# Wici_ski.net
KiCad netlist of a schematic drawn in EAGLE
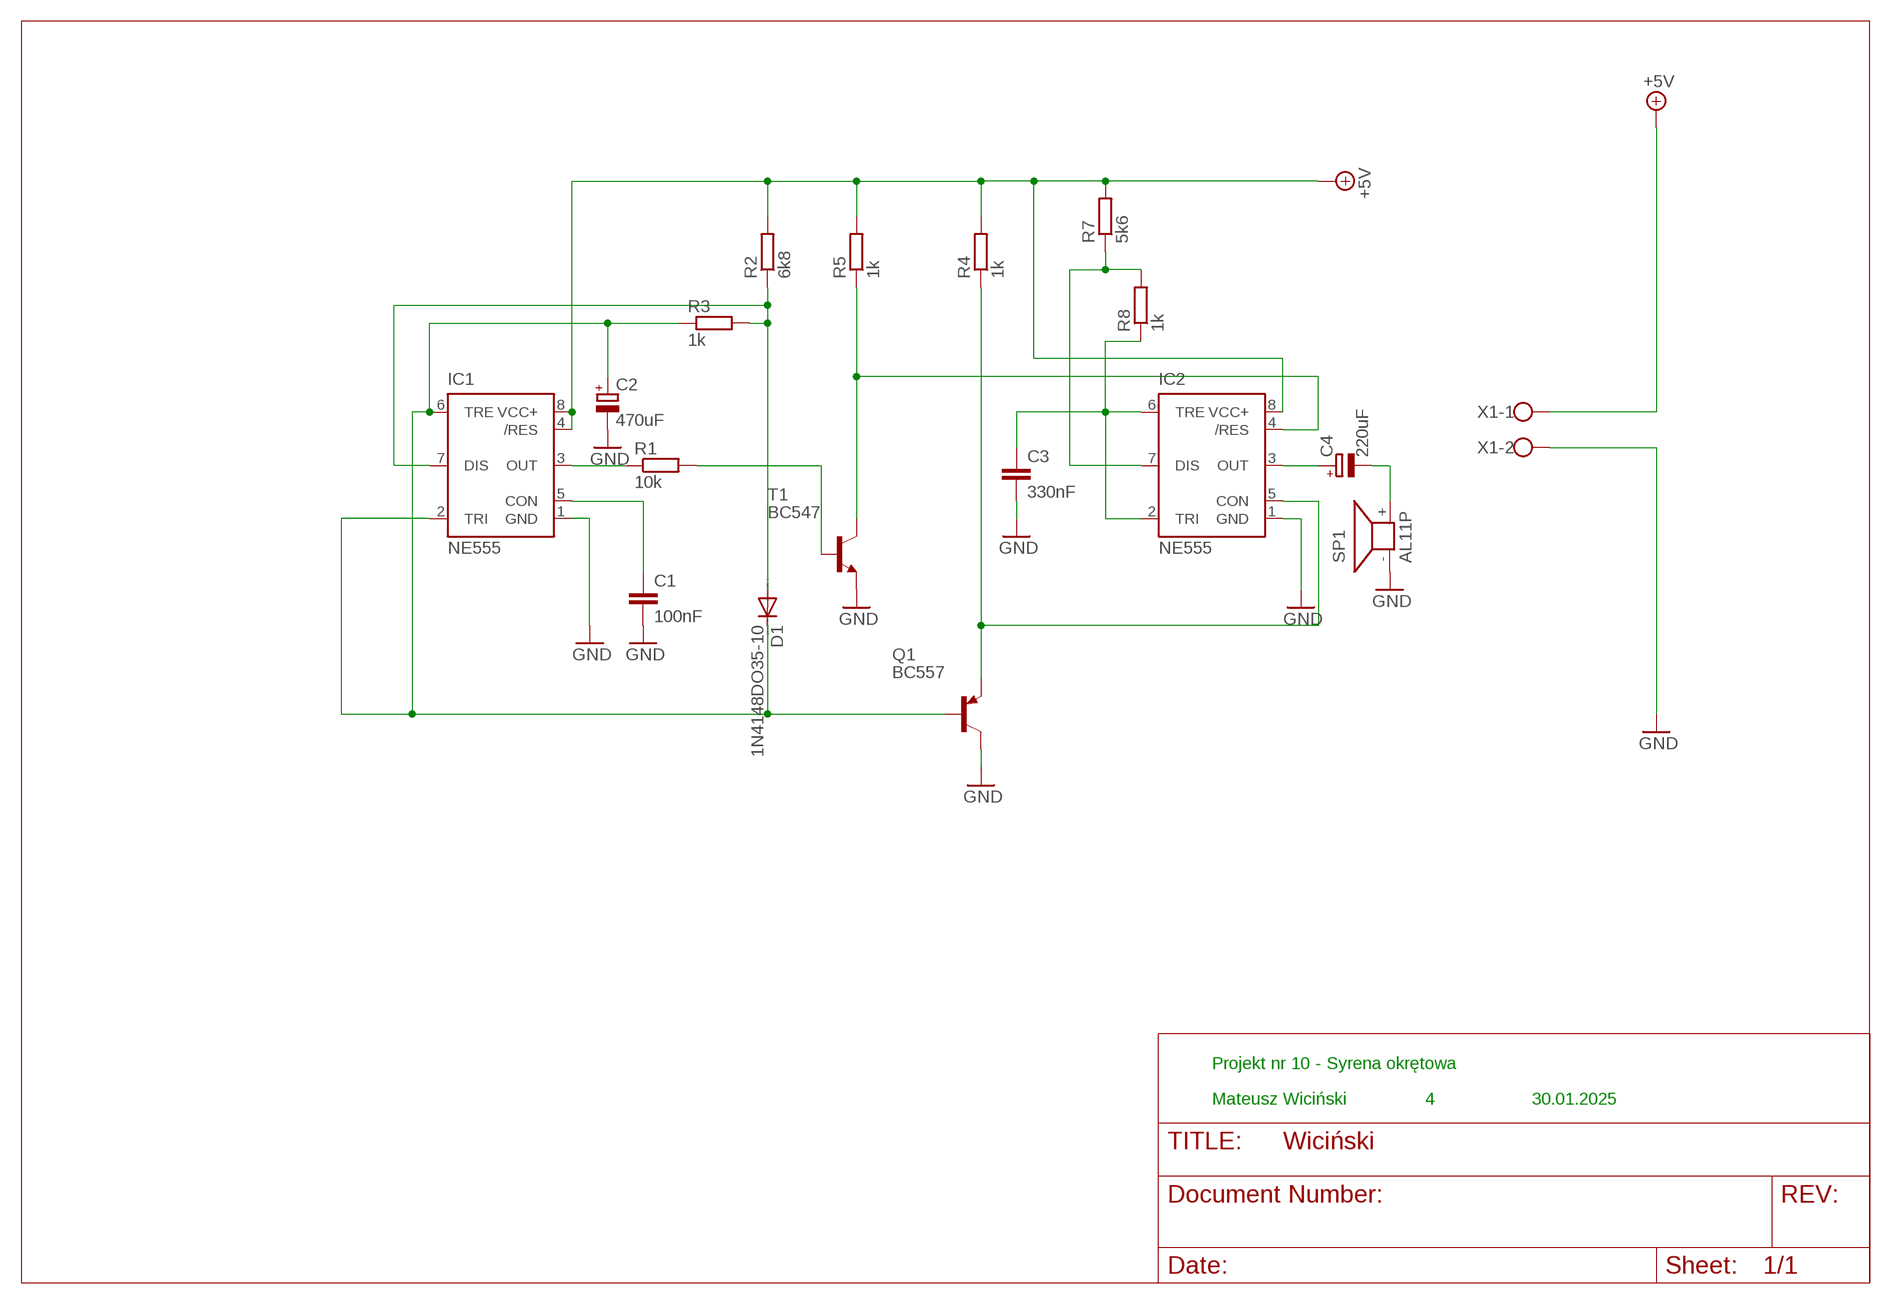
[diagram p0: schematic, sheet 1]

(export (version "E")
  (design (tool "Eeschema 10.0.6"))
  (components
    (comp (ref "C1")
      (value "100nF")
      (footprint "eagle-import:C050-050X075")
      (libsource (lib "eagle-import") (part "C-EU050-050X075"))
    )
    (comp (ref "C2")
      (value "470uF")
      (footprint "eagle-import:140CLH-1014")
      (libsource (lib "eagle-import") (part "CPOL-EU140CLH-1014"))
    )
    (comp (ref "C3")
      (value "330nF")
      (footprint "eagle-import:C050-050X075")
      (libsource (lib "eagle-import") (part "C-EU050-050X075"))
    )
    (comp (ref "C4")
      (value "220uF")
      (footprint "eagle-import:140CLH-1014")
      (libsource (lib "eagle-import") (part "CPOL-EU140CLH-1014"))
    )
    (comp (ref "D1")
      (value "1N4148DO35-10")
      (footprint "eagle-import:DO35-10")
      (libsource (lib "eagle-import") (part "1N4148DO35-10"))
    )
    (comp (ref "IC1")
      (value "NE555")
      (footprint "eagle-import:DIL-08")
      (fields (field (name "MF") "Arrow Electronics") (field (name "MPN") "NE555N"))
      (libsource (lib "eagle-import") (part "NE555"))
    )
    (comp (ref "IC2")
      (value "NE555")
      (footprint "eagle-import:DIL-08")
      (fields (field (name "MF") "Arrow Electronics") (field (name "MPN") "NE555N"))
      (libsource (lib "eagle-import") (part "NE555"))
    )
    (comp (ref "Q1")
      (value "BC557")
      (footprint "eagle-import:TO92")
      (libsource (lib "eagle-import") (part "BC557"))
    )
    (comp (ref "R1")
      (value "10k")
      (footprint "eagle-import:0207_10")
      (libsource (lib "eagle-import") (part "R-EU_0207/10"))
    )
    (comp (ref "R2")
      (value "6k8")
      (footprint "eagle-import:0207_10")
      (libsource (lib "eagle-import") (part "R-EU_0207/10"))
    )
    (comp (ref "R3")
      (value "1k")
      (footprint "eagle-import:0207_10")
      (libsource (lib "eagle-import") (part "R-EU_0207/10"))
    )
    (comp (ref "R4")
      (value "1k")
      (footprint "eagle-import:0207_10")
      (libsource (lib "eagle-import") (part "R-EU_0207/10"))
    )
    (comp (ref "R5")
      (value "1k")
      (footprint "eagle-import:0207_10")
      (libsource (lib "eagle-import") (part "R-EU_0207/10"))
    )
    (comp (ref "R7")
      (value "5k6")
      (footprint "eagle-import:0207_10")
      (libsource (lib "eagle-import") (part "R-EU_0207/10"))
    )
    (comp (ref "R8")
      (value "1k")
      (footprint "eagle-import:0207_10")
      (libsource (lib "eagle-import") (part "R-EU_0207/10"))
    )
    (comp (ref "SP1")
      (value "AL11P")
      (footprint "eagle-import:AL11P")
      (libsource (lib "eagle-import") (part "AL11P"))
    )
    (comp (ref "T1")
      (value "BC547")
      (footprint "eagle-import:TO92")
      (libsource (lib "eagle-import") (part "BC547"))
    )
    (comp (ref "X1")
      (value "W237-102")
      (footprint "eagle-import:W237-102")
      (fields (field (name "MPN") "237-102"))
      (libsource (lib "eagle-import") (part "W237-102"))
    )
  )
  (nets
    (net (code "1") (name "+5V") (class "Default")
      (node (ref "IC1") (pin "4") (pinfunction "/RES_4") (pintype "input"))
      (node (ref "IC1") (pin "8") (pinfunction "VCC+_8") (pintype "power_in"))
      (node (ref "IC2") (pin "8") (pinfunction "VCC+_8") (pintype "power_in"))
      (node (ref "R2") (pin "2") (pinfunction "2_2") (pintype "passive"))
      (node (ref "R4") (pin "2") (pinfunction "2_2") (pintype "passive"))
      (node (ref "R5") (pin "2") (pinfunction "2_2") (pintype "passive"))
      (node (ref "R7") (pin "2") (pinfunction "2_2") (pintype "passive"))
      (node (ref "X1") (pin "1") (pinfunction "KL_1") (pintype "passive"))
    )
    (net (code "2") (name "GND") (class "Default")
      (node (ref "C1") (pin "2") (pinfunction "2_2") (pintype "passive"))
      (node (ref "C2") (pin "-") (pinfunction "-_-") (pintype "passive"))
      (node (ref "C3") (pin "2") (pinfunction "2_2") (pintype "passive"))
      (node (ref "IC1") (pin "1") (pinfunction "GND_1") (pintype "power_in"))
      (node (ref "IC2") (pin "1") (pinfunction "GND_1") (pintype "power_in"))
      (node (ref "Q1") (pin "3") (pinfunction "C_3") (pintype "passive"))
      (node (ref "SP1") (pin "-") (pinfunction "1_-") (pintype "passive"))
      (node (ref "T1") (pin "1") (pinfunction "E_1") (pintype "passive"))
      (node (ref "X1") (pin "2") (pinfunction "KL_2") (pintype "passive"))
    )
    (net (code "3") (name "Net-(IC1-CON)") (class "Default")
      (node (ref "C1") (pin "1") (pinfunction "1_1") (pintype "passive"))
      (node (ref "IC1") (pin "5") (pinfunction "CON_5") (pintype "input"))
    )
    (net (code "4") (name "Net-(IC1-DIS)") (class "Default")
      (node (ref "D1") (pin "A") (pinfunction "A_A") (pintype "passive"))
      (node (ref "IC1") (pin "7") (pinfunction "DIS_7") (pintype "input"))
      (node (ref "R2") (pin "1") (pinfunction "1_1") (pintype "passive"))
      (node (ref "R3") (pin "2") (pinfunction "2_2") (pintype "passive"))
    )
    (net (code "5") (name "Net-(IC1-OUT)") (class "Default")
      (node (ref "IC1") (pin "3") (pinfunction "OUT_3") (pintype "output"))
      (node (ref "R1") (pin "1") (pinfunction "1_1") (pintype "passive"))
    )
    (net (code "6") (name "Net-(IC1-TRE)") (class "Default")
      (node (ref "C2") (pin "+") (pinfunction "+_+") (pintype "passive"))
      (node (ref "D1") (pin "C") (pinfunction "C_C") (pintype "passive"))
      (node (ref "IC1") (pin "2") (pinfunction "TRI_2") (pintype "input"))
      (node (ref "IC1") (pin "6") (pinfunction "TRE_6") (pintype "input"))
      (node (ref "Q1") (pin "2") (pinfunction "B_2") (pintype "passive"))
      (node (ref "R3") (pin "1") (pinfunction "1_1") (pintype "passive"))
    )
    (net (code "7") (name "Net-(IC2-CON)") (class "Default")
      (node (ref "IC2") (pin "5") (pinfunction "CON_5") (pintype "input"))
      (node (ref "Q1") (pin "1") (pinfunction "E_1") (pintype "passive"))
      (node (ref "R4") (pin "1") (pinfunction "1_1") (pintype "passive"))
    )
    (net (code "8") (name "Net-(IC2-DIS)") (class "Default")
      (node (ref "IC2") (pin "7") (pinfunction "DIS_7") (pintype "input"))
      (node (ref "R7") (pin "1") (pinfunction "1_1") (pintype "passive"))
      (node (ref "R8") (pin "2") (pinfunction "2_2") (pintype "passive"))
    )
    (net (code "9") (name "Net-(IC2-OUT)") (class "Default")
      (node (ref "C4") (pin "+") (pinfunction "+_+") (pintype "passive"))
      (node (ref "IC2") (pin "3") (pinfunction "OUT_3") (pintype "output"))
    )
    (net (code "10") (name "Net-(IC2-TRE)") (class "Default")
      (node (ref "C3") (pin "1") (pinfunction "1_1") (pintype "passive"))
      (node (ref "IC2") (pin "2") (pinfunction "TRI_2") (pintype "input"))
      (node (ref "IC2") (pin "6") (pinfunction "TRE_6") (pintype "input"))
      (node (ref "R8") (pin "1") (pinfunction "1_1") (pintype "passive"))
    )
    (net (code "11") (name "Net-(IC2-{slash}RES)") (class "Default")
      (node (ref "IC2") (pin "4") (pinfunction "/RES_4") (pintype "input"))
      (node (ref "R5") (pin "1") (pinfunction "1_1") (pintype "passive"))
      (node (ref "T1") (pin "3") (pinfunction "C_3") (pintype "passive"))
    )
    (net (code "12") (name "Net-(SP1-2)") (class "Default")
      (node (ref "C4") (pin "-") (pinfunction "-_-") (pintype "passive"))
      (node (ref "SP1") (pin "+") (pinfunction "2_+") (pintype "passive"))
    )
    (net (code "13") (name "Net-(T1-B)") (class "Default")
      (node (ref "R1") (pin "2") (pinfunction "2_2") (pintype "passive"))
      (node (ref "T1") (pin "2") (pinfunction "B_2") (pintype "passive"))
    )
  )
)
